# probe_v2.net
KiCad netlist of a schematic drawn in EAGLE
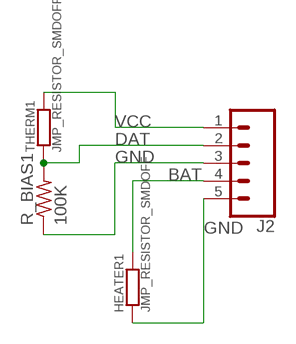
[diagram p0: schematic, sheet 1]

(export (version "E")
  (design (tool "Eeschema 10.0.6"))
  (components
    (comp (ref "HEATER1")
      (value "JMP_RESISTOR_SMDOFF")
      (footprint "eagle-import:JMP_OFF_SMD")
      (libsource (lib "eagle-import") (part "JMP_RESISTOR_SMDOFF"))
    )
    (comp (ref "J2")
      (value "CONN_05NO_SILK")
      (footprint "eagle-import:1X05_NO_SILK")
      (libsource (lib "eagle-import") (part "CONN_05NO_SILK"))
    )
    (comp (ref "R_BIAS1")
      (value "100K")
      (footprint "eagle-import:0805-THM")
      (libsource (lib "eagle-import") (part "FLIPFLOP-RES"))
    )
    (comp (ref "THERM1")
      (value "JMP_RESISTOR_SMDOFF")
      (footprint "eagle-import:JMP_OFF_SMD")
      (libsource (lib "eagle-import") (part "JMP_RESISTOR_SMDOFF"))
    )
  )
  (nets
    (net (code "1") (name "/BAT") (class "Default")
      (node (ref "HEATER1") (pin "2") (pinfunction "P$2_2") (pintype "bidirectional"))
      (node (ref "J2") (pin "4") (pinfunction "4_4") (pintype "passive"))
    )
    (net (code "2") (name "/DAT") (class "Default")
      (node (ref "J2") (pin "2") (pinfunction "2_2") (pintype "passive"))
      (node (ref "R_BIAS1") (pin "2") (pinfunction "2_2") (pintype "passive"))
      (node (ref "THERM1") (pin "1") (pinfunction "P$1_1") (pintype "bidirectional"))
    )
    (net (code "3") (name "/GND") (class "Default")
      (node (ref "HEATER1") (pin "1") (pinfunction "P$1_1") (pintype "bidirectional"))
      (node (ref "J2") (pin "3") (pinfunction "3_3") (pintype "passive"))
      (node (ref "J2") (pin "5") (pinfunction "5_5") (pintype "passive"))
      (node (ref "R_BIAS1") (pin "1") (pinfunction "1_1") (pintype "passive"))
    )
    (net (code "4") (name "/VCC") (class "Default")
      (node (ref "J2") (pin "1") (pinfunction "1_1") (pintype "passive"))
      (node (ref "THERM1") (pin "2") (pinfunction "P$2_2") (pintype "bidirectional"))
    )
  )
)
